# PicoMiteVGAV1_1.net
KiCad netlist of a schematic drawn in EasyEDA Pro
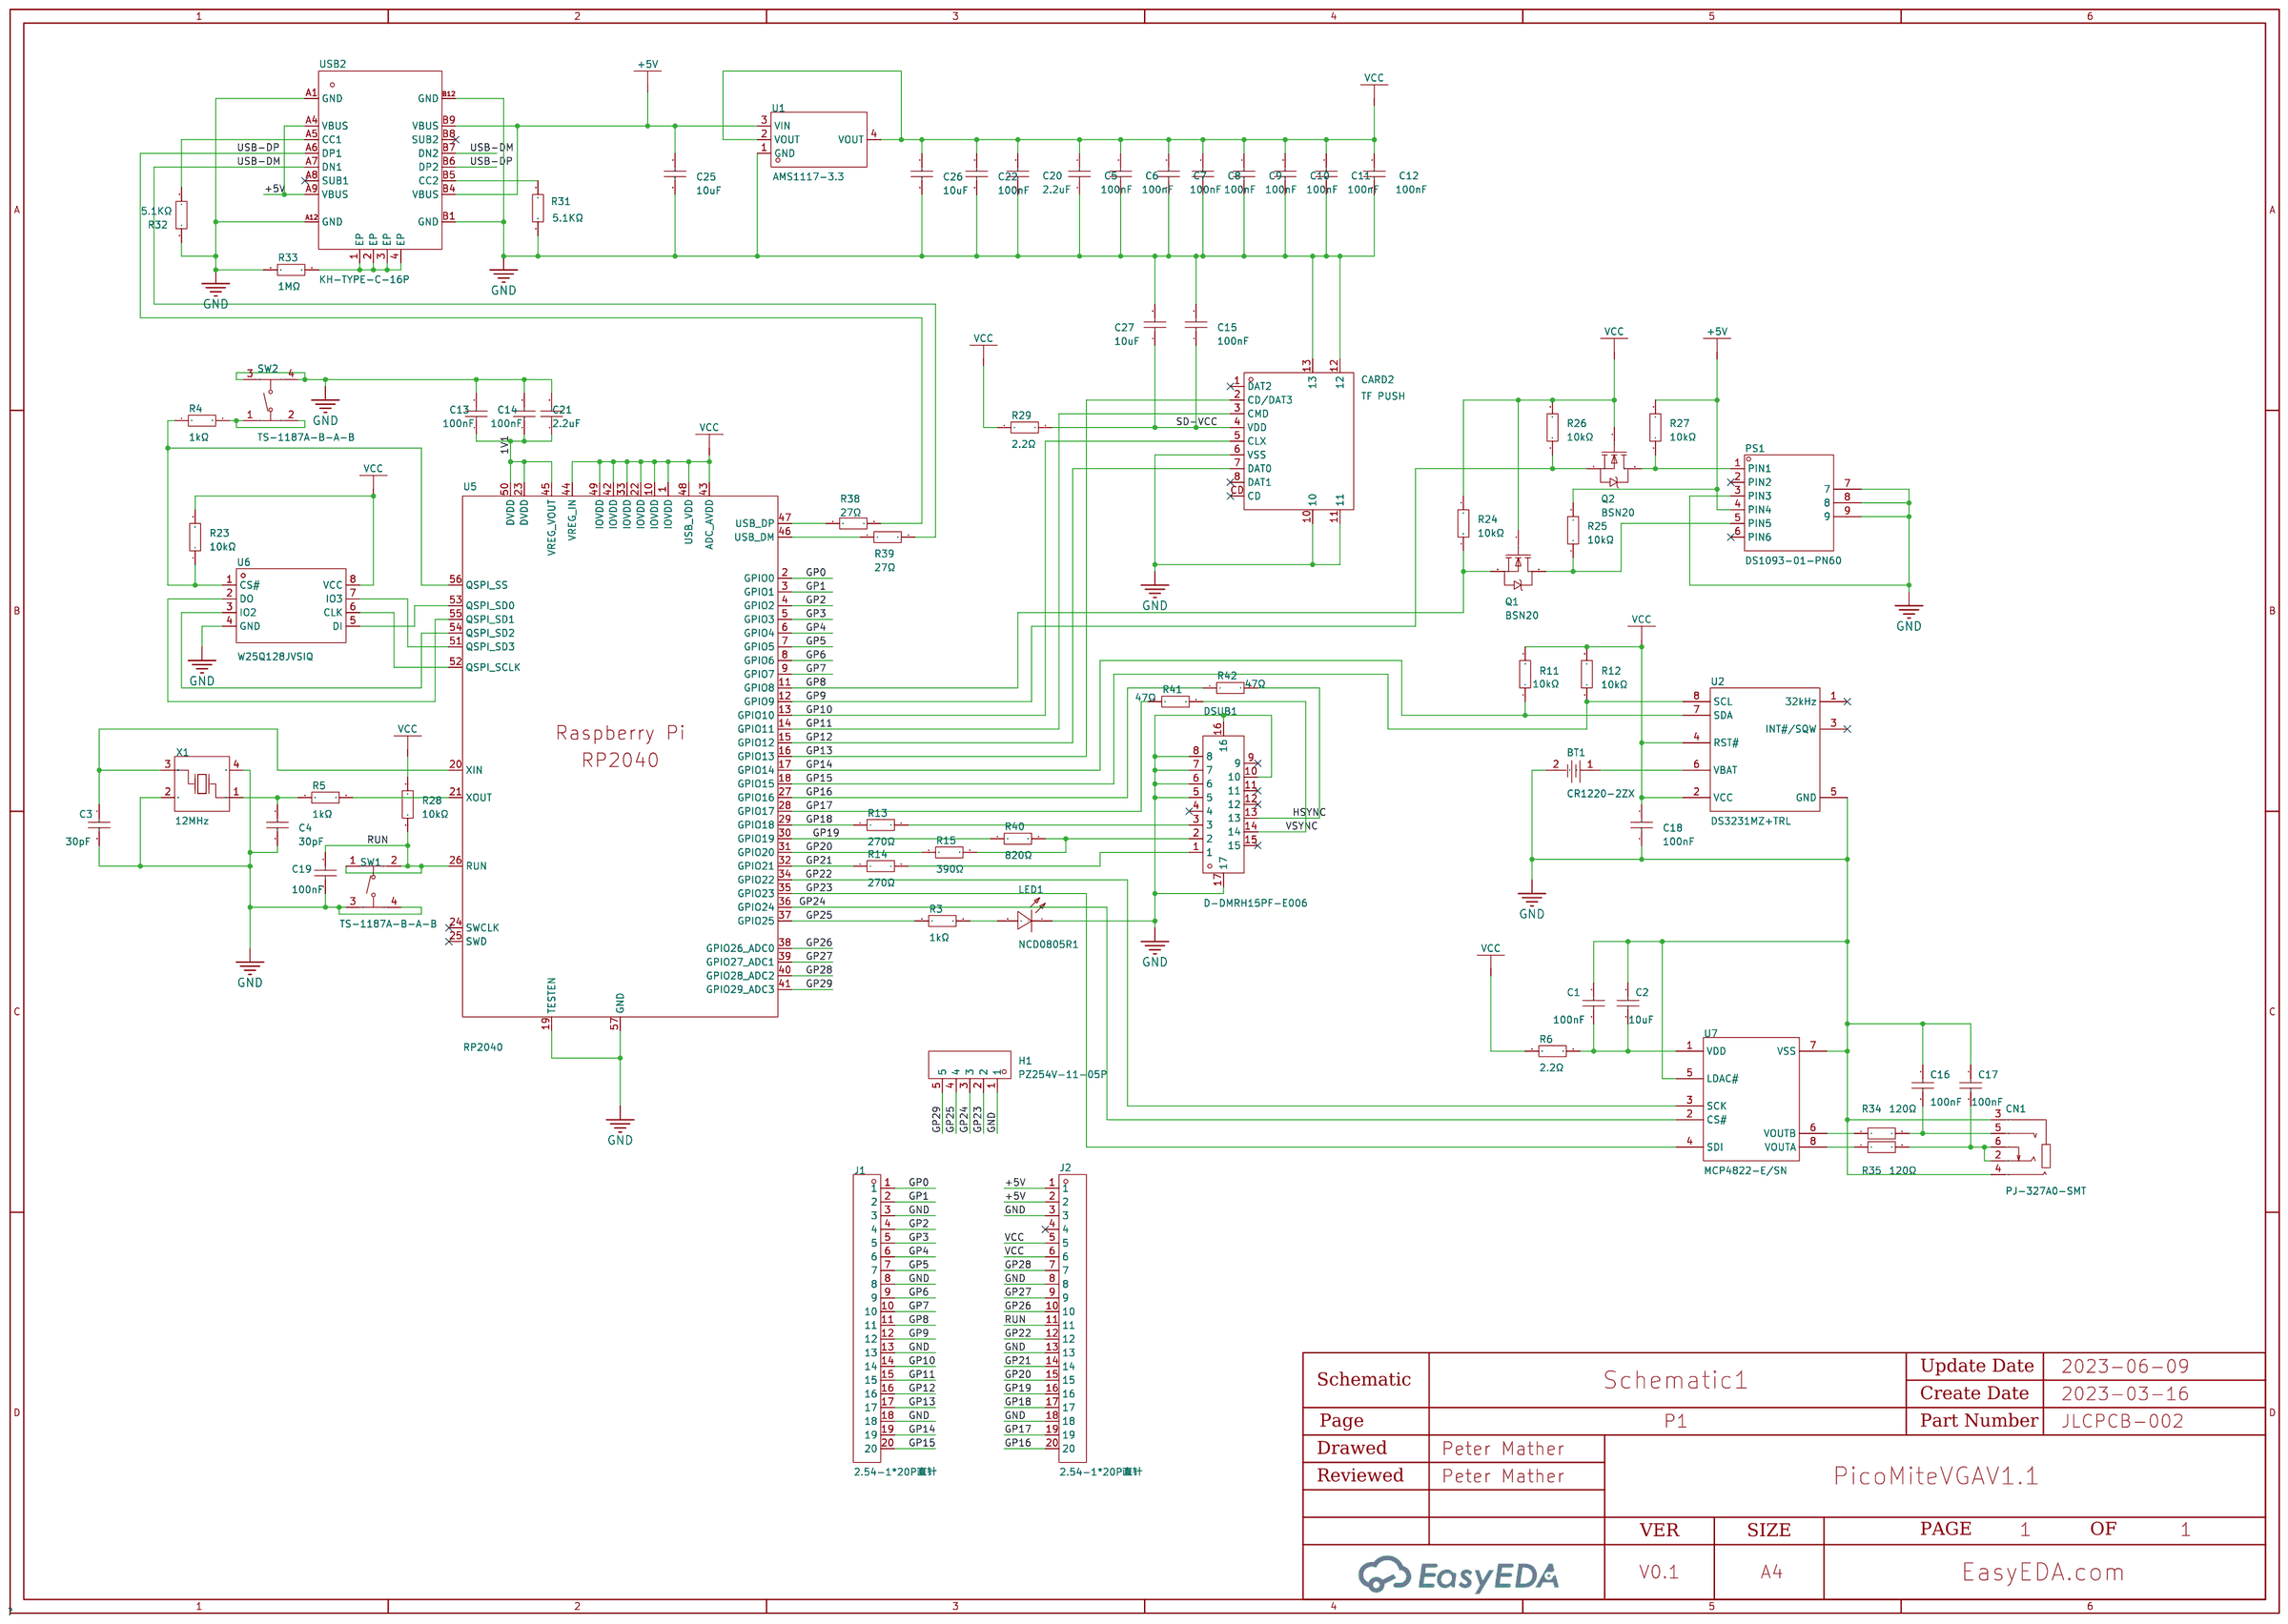
[diagram p0: schematic sheet]

(export (version "E")
  (design (tool "Eeschema 10.0.6"))
  (components
    (comp (ref "BT1")
      (value "CR1220-2ZX")
      (footprint "easyedapro:BAT-SMD_CR1220-2ZX")
      (fields (field (name "Manufacturer") "Q&J"))
      (libsource (lib "easyedapro") (part "CR1220-2ZX"))
    )
    (comp (ref "C1")
      (value "100nF")
      (footprint "easyedapro:C0603")
      (fields
        (field (name "Manufacturer Part") "CL05B104KO5NNNC")
        (field (name "Manufacturer") "SAMSUNG(三星)")
      )
      (libsource (lib "easyedapro") (part "CL10A225KO8NNNC"))
    )
    (comp (ref "C2")
      (value "10uF")
      (footprint "easyedapro:C1206")
      (fields
        (field (name "Manufacturer Part") "CL31A106KBHNNNE")
        (field (name "Manufacturer") "SAMSUNG(三星)")
      )
      (libsource (lib "easyedapro") (part "CL31A106KBHNNNE"))
    )
    (comp (ref "C3")
      (value "30pF")
      (footprint "easyedapro:C0805")
      (fields (field (name "Manufacturer Part") "0402CG300J500NT") (field (name "Manufacturer") "FH(风华)"))
      (libsource (lib "easyedapro") (part "CC0805JRNPO9BN300"))
    )
    (comp (ref "C4")
      (value "30pF")
      (footprint "easyedapro:C0805")
      (fields (field (name "Manufacturer Part") "0402CG300J500NT") (field (name "Manufacturer") "FH(风华)"))
      (libsource (lib "easyedapro") (part "CC0805JRNPO9BN300"))
    )
    (comp (ref "C5")
      (value "100nF")
      (footprint "easyedapro:C0603")
      (fields
        (field (name "Manufacturer Part") "CL05B104KO5NNNC")
        (field (name "Manufacturer") "SAMSUNG(三星)")
      )
      (libsource (lib "easyedapro") (part "CL10A225KO8NNNC"))
    )
    (comp (ref "C6")
      (value "100nF")
      (footprint "easyedapro:C0603")
      (fields
        (field (name "Manufacturer Part") "CL05B104KO5NNNC")
        (field (name "Manufacturer") "SAMSUNG(三星)")
      )
      (libsource (lib "easyedapro") (part "CL10A225KO8NNNC"))
    )
    (comp (ref "C7")
      (value "100nF")
      (footprint "easyedapro:C0603")
      (fields
        (field (name "Manufacturer Part") "CL05B104KO5NNNC")
        (field (name "Manufacturer") "SAMSUNG(三星)")
      )
      (libsource (lib "easyedapro") (part "CL10A225KO8NNNC"))
    )
    (comp (ref "C8")
      (value "100nF")
      (footprint "easyedapro:C0603")
      (fields
        (field (name "Manufacturer Part") "CL05B104KO5NNNC")
        (field (name "Manufacturer") "SAMSUNG(三星)")
      )
      (libsource (lib "easyedapro") (part "CL10A225KO8NNNC"))
    )
    (comp (ref "C9")
      (value "100nF")
      (footprint "easyedapro:C0603")
      (fields
        (field (name "Manufacturer Part") "CL05B104KO5NNNC")
        (field (name "Manufacturer") "SAMSUNG(三星)")
      )
      (libsource (lib "easyedapro") (part "CL10A225KO8NNNC"))
    )
    (comp (ref "C10")
      (value "100nF")
      (footprint "easyedapro:C0603")
      (fields
        (field (name "Manufacturer Part") "CL05B104KO5NNNC")
        (field (name "Manufacturer") "SAMSUNG(三星)")
      )
      (libsource (lib "easyedapro") (part "CL10A225KO8NNNC"))
    )
    (comp (ref "C11")
      (value "100nF")
      (footprint "easyedapro:C0603")
      (fields
        (field (name "Manufacturer Part") "CL05B104KO5NNNC")
        (field (name "Manufacturer") "SAMSUNG(三星)")
      )
      (libsource (lib "easyedapro") (part "CL10A225KO8NNNC"))
    )
    (comp (ref "C12")
      (value "100nF")
      (footprint "easyedapro:C0603")
      (fields
        (field (name "Manufacturer Part") "CL05B104KO5NNNC")
        (field (name "Manufacturer") "SAMSUNG(三星)")
      )
      (libsource (lib "easyedapro") (part "CL10A225KO8NNNC"))
    )
    (comp (ref "C13")
      (value "100nF")
      (footprint "easyedapro:C0603")
      (fields
        (field (name "Manufacturer Part") "CL05B104KO5NNNC")
        (field (name "Manufacturer") "SAMSUNG(三星)")
      )
      (libsource (lib "easyedapro") (part "CL10A225KO8NNNC"))
    )
    (comp (ref "C14")
      (value "100nF")
      (footprint "easyedapro:C0603")
      (fields
        (field (name "Manufacturer Part") "CL05B104KO5NNNC")
        (field (name "Manufacturer") "SAMSUNG(三星)")
      )
      (libsource (lib "easyedapro") (part "CL10A225KO8NNNC"))
    )
    (comp (ref "C15")
      (value "100nF")
      (footprint "easyedapro:C0603")
      (fields
        (field (name "Manufacturer Part") "CL05B104KO5NNNC")
        (field (name "Manufacturer") "SAMSUNG(三星)")
      )
      (libsource (lib "easyedapro") (part "CL10A225KO8NNNC"))
    )
    (comp (ref "C16")
      (value "100nF")
      (footprint "easyedapro:C0603")
      (fields
        (field (name "Manufacturer Part") "CL05B104KO5NNNC")
        (field (name "Manufacturer") "SAMSUNG(三星)")
      )
      (libsource (lib "easyedapro") (part "CL10A225KO8NNNC"))
    )
    (comp (ref "C17")
      (value "100nF")
      (footprint "easyedapro:C0603")
      (fields
        (field (name "Manufacturer Part") "CL05B104KO5NNNC")
        (field (name "Manufacturer") "SAMSUNG(三星)")
      )
      (libsource (lib "easyedapro") (part "CL10A225KO8NNNC"))
    )
    (comp (ref "C18")
      (value "100nF")
      (footprint "easyedapro:C0603")
      (fields
        (field (name "Manufacturer Part") "CL05B104KO5NNNC")
        (field (name "Manufacturer") "SAMSUNG(三星)")
      )
      (libsource (lib "easyedapro") (part "CL10A225KO8NNNC"))
    )
    (comp (ref "C19")
      (value "100nF")
      (footprint "easyedapro:C0603")
      (fields
        (field (name "Manufacturer Part") "CL05B104KO5NNNC")
        (field (name "Manufacturer") "SAMSUNG(三星)")
      )
      (libsource (lib "easyedapro") (part "CL10A225KO8NNNC"))
    )
    (comp (ref "C20")
      (value "2.2uF")
      (footprint "easyedapro:C0402_NEW")
      (fields
        (field (name "Manufacturer Part") "CL10A225KO8NNNC")
        (field (name "Manufacturer") "SAMSUNG(三星)")
      )
      (libsource (lib "easyedapro") (part "CL05B104KO5NNNC"))
    )
    (comp (ref "C21")
      (value "2.2uF")
      (footprint "easyedapro:C0402_NEW")
      (fields
        (field (name "Manufacturer Part") "CL10A225KO8NNNC")
        (field (name "Manufacturer") "SAMSUNG(三星)")
      )
      (libsource (lib "easyedapro") (part "CL05B104KO5NNNC"))
    )
    (comp (ref "C22")
      (value "100nF")
      (footprint "easyedapro:C0603")
      (fields
        (field (name "Manufacturer Part") "CL05B104KO5NNNC")
        (field (name "Manufacturer") "SAMSUNG(三星)")
      )
      (libsource (lib "easyedapro") (part "CL10A225KO8NNNC"))
    )
    (comp (ref "C25")
      (value "10uF")
      (footprint "easyedapro:C1206")
      (fields
        (field (name "Manufacturer Part") "CL31A106KBHNNNE")
        (field (name "Manufacturer") "SAMSUNG(三星)")
      )
      (libsource (lib "easyedapro") (part "CL31A106KBHNNNE"))
    )
    (comp (ref "C26")
      (value "10uF")
      (footprint "easyedapro:C1206")
      (fields
        (field (name "Manufacturer Part") "CL31A106KBHNNNE")
        (field (name "Manufacturer") "SAMSUNG(三星)")
      )
      (libsource (lib "easyedapro") (part "CL31A106KBHNNNE"))
    )
    (comp (ref "C27")
      (value "10uF")
      (footprint "easyedapro:C1206")
      (fields
        (field (name "Manufacturer Part") "CL31A106KBHNNNE")
        (field (name "Manufacturer") "SAMSUNG(三星)")
      )
      (libsource (lib "easyedapro") (part "CL31A106KBHNNNE"))
    )
    (comp (ref "CARD2")
      (value "TF PUSH")
      (footprint "easyedapro:TF-SMD_TF-PUSH")
      (fields (field (name "Manufacturer") "SHOU HAN(首韩)"))
      (libsource (lib "easyedapro") (part "TF PUSH"))
    )
    (comp (ref "CN1")
      (value "PJ-327A0-SMT")
      (footprint "easyedapro:AUDIO-SMD_PJ-327A0-SMT")
      (fields (field (name "Manufacturer") "XKB Connectivity(中国星坤)"))
      (libsource (lib "easyedapro") (part "PJ-327A0-SMT"))
    )
    (comp (ref "DSUB1")
      (value "D-DMRH15PF-E006")
      (footprint "easyedapro:DSUB-TH_15P-P2.29-H-F_DDMRH15PFE006")
      (fields (field (name "Manufacturer") "Ckmtw(灿科盟)"))
      (libsource (lib "easyedapro") (part "DDMRH15PFE006"))
    )
    (comp (ref "H1")
      (value "PZ254V-11-05P")
      (footprint "easyedapro:HDR-TH_5P-P2.54-V-M")
      (fields (field (name "Manufacturer") "XFCN(兴飞)"))
      (libsource (lib "easyedapro") (part "PZ254V-11-05P"))
    )
    (comp (ref "J1")
      (value "2.54-1*20P直针")
      (footprint "easyedapro:HDR-TH_20P-P2.54-V-M-1")
      (fields (field (name "Manufacturer") "BOOMELE(博穆精密)"))
      (libsource (lib "easyedapro") (part "Header-Male-2.54_1x20"))
    )
    (comp (ref "J2")
      (value "2.54-1*20P直针")
      (footprint "easyedapro:HDR-TH_20P-P2.54-V-M-1")
      (fields (field (name "Manufacturer") "BOOMELE(博穆精密)"))
      (libsource (lib "easyedapro") (part "Header-Male-2.54_1x20"))
    )
    (comp (ref "LED1")
      (value "NCD0805R1")
      (footprint "easyedapro:LED0805-RD")
      (description "Emitted Color:红灯")
      (fields (field (name "Manufacturer") "国星光电"))
      (libsource (lib "easyedapro") (part "FC-2012HRK-620D"))
    )
    (comp (ref "PS1")
      (value "DS1093-01-PN60")
      (footprint "easyedapro:CONN-TH_DS1093-01-PN60")
      (fields (field (name "Manufacturer") "CONNFLY"))
      (libsource (lib "easyedapro") (part "DS1093-01-PN60"))
    )
    (comp (ref "Q1")
      (value "BSN20")
      (footprint "easyedapro:SOT-23-3_L2.9-W1.6-P1.90-LS2.8-BR")
      (fields (field (name "Manufacturer") "SHIKUES(时科)"))
      (libsource (lib "easyedapro") (part "BSN20"))
    )
    (comp (ref "Q2")
      (value "BSN20")
      (footprint "easyedapro:SOT-23-3_L2.9-W1.6-P1.90-LS2.8-BR")
      (fields (field (name "Manufacturer") "SHIKUES(时科)"))
      (libsource (lib "easyedapro") (part "BSN20"))
    )
    (comp (ref "R3")
      (value "1kΩ")
      (footprint "easyedapro:R0603")
      (fields
        (field (name "Manufacturer Part") "0603WAF1001T5E")
        (field (name "Manufacturer") "UNI-ROYAL(厚声)")
      )
      (libsource (lib "easyedapro") (part "0603WAF1001T5E"))
    )
    (comp (ref "R4")
      (value "1kΩ")
      (footprint "easyedapro:R0603")
      (fields
        (field (name "Manufacturer Part") "0603WAF1001T5E")
        (field (name "Manufacturer") "UNI-ROYAL(厚声)")
      )
      (libsource (lib "easyedapro") (part "0603WAF1001T5E"))
    )
    (comp (ref "R5")
      (value "1kΩ")
      (footprint "easyedapro:R0603")
      (fields
        (field (name "Manufacturer Part") "0603WAF1001T5E")
        (field (name "Manufacturer") "UNI-ROYAL(厚声)")
      )
      (libsource (lib "easyedapro") (part "0603WAF1001T5E"))
    )
    (comp (ref "R6")
      (value "2.2Ω")
      (footprint "easyedapro:R0805")
      (fields (field (name "Manufacturer") "UNI-ROYAL(厚声)"))
      (libsource (lib "easyedapro") (part "0805W8F220KT5E"))
    )
    (comp (ref "R11")
      (value "10kΩ")
      (footprint "easyedapro:R0805")
      (fields
        (field (name "Manufacturer Part") "0805W8F1002T5E")
        (field (name "Manufacturer") "UNI-ROYAL(厚声)")
      )
      (libsource (lib "easyedapro") (part "0805W8F1002T5E"))
    )
    (comp (ref "R12")
      (value "10kΩ")
      (footprint "easyedapro:R0805")
      (fields
        (field (name "Manufacturer Part") "0805W8F1002T5E")
        (field (name "Manufacturer") "UNI-ROYAL(厚声)")
      )
      (libsource (lib "easyedapro") (part "0805W8F1002T5E"))
    )
    (comp (ref "R13")
      (value "270Ω")
      (footprint "easyedapro:R0603")
      (fields
        (field (name "Manufacturer Part") "0603WAF2700T5E")
        (field (name "Manufacturer") "UNI-ROYAL(厚声)")
      )
      (libsource (lib "easyedapro") (part "0603WAF2700T5E"))
    )
    (comp (ref "R14")
      (value "270Ω")
      (footprint "easyedapro:R0603")
      (fields
        (field (name "Manufacturer Part") "0603WAF2700T5E")
        (field (name "Manufacturer") "UNI-ROYAL(厚声)")
      )
      (libsource (lib "easyedapro") (part "0603WAF2700T5E"))
    )
    (comp (ref "R15")
      (value "390Ω")
      (footprint "easyedapro:R0603")
      (fields
        (field (name "Manufacturer Part") "0603WAF3900T5E")
        (field (name "Manufacturer") "UNI-ROYAL(厚声)")
      )
      (libsource (lib "easyedapro") (part "0603WAF3900T5E"))
    )
    (comp (ref "R23")
      (value "10kΩ")
      (footprint "easyedapro:R0402")
      (fields
        (field (name "Manufacturer Part") "0402WGF1002TCE")
        (field (name "Manufacturer") "UNI-ROYAL(厚声)")
      )
      (libsource (lib "easyedapro") (part "0402WGF1002TCE"))
    )
    (comp (ref "R24")
      (value "10kΩ")
      (footprint "easyedapro:R0402")
      (fields
        (field (name "Manufacturer Part") "0402WGF1002TCE")
        (field (name "Manufacturer") "UNI-ROYAL(厚声)")
      )
      (libsource (lib "easyedapro") (part "0402WGF1002TCE"))
    )
    (comp (ref "R25")
      (value "10kΩ")
      (footprint "easyedapro:R0402")
      (fields
        (field (name "Manufacturer Part") "0402WGF1002TCE")
        (field (name "Manufacturer") "UNI-ROYAL(厚声)")
      )
      (libsource (lib "easyedapro") (part "0402WGF1002TCE"))
    )
    (comp (ref "R26")
      (value "10kΩ")
      (footprint "easyedapro:R0402")
      (fields
        (field (name "Manufacturer Part") "0402WGF1002TCE")
        (field (name "Manufacturer") "UNI-ROYAL(厚声)")
      )
      (libsource (lib "easyedapro") (part "0402WGF1002TCE"))
    )
    (comp (ref "R27")
      (value "10kΩ")
      (footprint "easyedapro:R0402")
      (fields
        (field (name "Manufacturer Part") "0402WGF1002TCE")
        (field (name "Manufacturer") "UNI-ROYAL(厚声)")
      )
      (libsource (lib "easyedapro") (part "0402WGF1002TCE"))
    )
    (comp (ref "R28")
      (value "10kΩ")
      (footprint "easyedapro:R0402")
      (fields
        (field (name "Manufacturer Part") "0402WGF1002TCE")
        (field (name "Manufacturer") "UNI-ROYAL(厚声)")
      )
      (libsource (lib "easyedapro") (part "0402WGF1002TCE"))
    )
    (comp (ref "R29")
      (value "2.2Ω")
      (footprint "easyedapro:R0805")
      (fields (field (name "Manufacturer") "UNI-ROYAL(厚声)"))
      (libsource (lib "easyedapro") (part "0805W8F220KT5E"))
    )
    (comp (ref "R31")
      (value "5.1kΩ")
      (footprint "easyedapro:R0603")
      (fields
        (field (name "Manufacturer Part") "5.1KΩ")
        (field (name "Manufacturer") "UNI-ROYAL(厚声)")
        (field (name "Tolerance") "±1%")
      )
      (libsource (lib "easyedapro") (part "0603WAF5101T5E"))
    )
    (comp (ref "R32")
      (value "5.1kΩ")
      (footprint "easyedapro:R0603")
      (fields
        (field (name "Manufacturer Part") "5.1KΩ")
        (field (name "Manufacturer") "UNI-ROYAL(厚声)")
        (field (name "Tolerance") "±1%")
      )
      (libsource (lib "easyedapro") (part "0603WAF5101T5E"))
    )
    (comp (ref "R33")
      (value "1MΩ")
      (footprint "easyedapro:R0603")
      (fields
        (field (name "Manufacturer Part") "0402WGF1004TCE")
        (field (name "Manufacturer") "UNI-ROYAL(厚声)")
        (field (name "Tolerance") "±1%")
      )
      (libsource (lib "easyedapro") (part "0603WAF1004T5E"))
    )
    (comp (ref "R34")
      (value "120Ω")
      (footprint "easyedapro:R0603")
      (fields
        (field (name "Manufacturer Part") "0603WAF1200T5E")
        (field (name "Manufacturer") "UNI-ROYAL(厚声)")
      )
      (libsource (lib "easyedapro") (part "0603WAF1200T5E"))
    )
    (comp (ref "R35")
      (value "120Ω")
      (footprint "easyedapro:R0603")
      (fields
        (field (name "Manufacturer Part") "0603WAF1200T5E")
        (field (name "Manufacturer") "UNI-ROYAL(厚声)")
      )
      (libsource (lib "easyedapro") (part "0603WAF1200T5E"))
    )
    (comp (ref "R38")
      (value "27Ω")
      (footprint "easyedapro:R0603")
      (fields
        (field (name "Manufacturer Part") "0603WAF270JT5E")
        (field (name "Manufacturer") "UNI-ROYAL(厚声)")
      )
      (libsource (lib "easyedapro") (part "0603WAF270JT5E"))
    )
    (comp (ref "R39")
      (value "27Ω")
      (footprint "easyedapro:R0603")
      (fields
        (field (name "Manufacturer Part") "0603WAF270JT5E")
        (field (name "Manufacturer") "UNI-ROYAL(厚声)")
      )
      (libsource (lib "easyedapro") (part "0603WAF270JT5E"))
    )
    (comp (ref "R40")
      (value "820Ω")
      (footprint "easyedapro:R0603")
      (fields
        (field (name "Manufacturer Part") "0603WAF8200T5E")
        (field (name "Manufacturer") "UNI-ROYAL(厚声)")
      )
      (libsource (lib "easyedapro") (part "0603WAF8200T5E"))
    )
    (comp (ref "R41")
      (value "47Ω")
      (footprint "easyedapro:R0805")
      (fields
        (field (name "Manufacturer Part") "0805W8F470JT5E")
        (field (name "Manufacturer") "UNI-ROYAL(厚声)")
      )
      (libsource (lib "easyedapro") (part "0805W8F470JT5E"))
    )
    (comp (ref "R42")
      (value "47Ω")
      (footprint "easyedapro:R0805")
      (fields
        (field (name "Manufacturer Part") "0805W8F470JT5E")
        (field (name "Manufacturer") "UNI-ROYAL(厚声)")
      )
      (libsource (lib "easyedapro") (part "0805W8F470JT5E"))
    )
    (comp (ref "SW1")
      (value "TS-1187A-B-A-B")
      (footprint "easyedapro:SW-SMD_4P-L5.1-W5.1-P3.70-LS6.5-TL-2")
      (fields (field (name "Manufacturer") "XKB Connectivity(中国星坤)"))
      (libsource (lib "easyedapro") (part "TS-1187A-B-A-B"))
    )
    (comp (ref "SW2")
      (value "TS-1187A-B-A-B")
      (footprint "easyedapro:SW-SMD_4P-L5.1-W5.1-P3.70-LS6.5-TL-2")
      (fields (field (name "Manufacturer") "XKB Connectivity(中国星坤)"))
      (libsource (lib "easyedapro") (part "TS-1187A-B-A-B"))
    )
    (comp (ref "U1")
      (value "AMS1117-3.3")
      (footprint "easyedapro:SOT-223-3_L6.5-W3.4-P2.30-LS7.0-BR")
      (fields (field (name "Manufacturer") "AMS"))
      (libsource (lib "easyedapro") (part "AMS1117-3.3"))
    )
    (comp (ref "U2")
      (value "DS3231MZ+TRL")
      (footprint "easyedapro:SOIC-8_L4.9-W3.9-P1.27-LS6.0-BL")
      (fields (field (name "Manufacturer") "MAXIM(美信)"))
      (libsource (lib "easyedapro") (part "DS3231MZ+"))
    )
    (comp (ref "U5")
      (value "RP2040")
      (footprint "easyedapro:LQFN-56_L7.0-W7.0-P0.4-EP")
      (fields (field (name "Manufacturer") "Raspberry Pi(树莓派)"))
      (libsource (lib "easyedapro") (part "RP2040"))
    )
    (comp (ref "U6")
      (value "W25Q128JVSIQ")
      (footprint "easyedapro:SOIC-8_L5.3-W5.3-P1.27-LS8.0-BL")
      (fields (field (name "Manufacturer") "WINBOND(华邦)"))
      (libsource (lib "easyedapro") (part "W25Q128JVSIQTR"))
    )
    (comp (ref "U7")
      (value "MCP4822-E/SN")
      (footprint "easyedapro:SOIC-8_L4.9-W3.9-P1.27-LS6.0-BL")
      (fields (field (name "Manufacturer") "MICROCHIP(美国微芯)"))
      (libsource (lib "easyedapro") (part "MCP4822-E/SN"))
    )
    (comp (ref "USB2")
      (value "KH-TYPE-C-16P")
      (footprint "easyedapro:USB-C-SMD_KH-TYPE-C-16P")
      (fields (field (name "Manufacturer") "kinghelm(金航标)"))
      (libsource (lib "easyedapro") (part "KH-TYPE-C-16P"))
    )
    (comp (ref "X1")
      (value "12MHz")
      (footprint "easyedapro:OSC-SMD_4P-L3.2-W2.5-BL")
      (fields (field (name "Manufacturer Part") "X322512MSB4SI") (field (name "Manufacturer") "YXC(扬兴晶振)"))
      (libsource (lib "easyedapro") (part "X322512MSB4SI"))
    )
  )
  (nets
    (net (code "1") (name "+5V") (class "Default")
      (node (ref "C25") (pin "2") (pinfunction "2_2") (pintype "input"))
      (node (ref "J2") (pin "1") (pinfunction "1_1") (pintype "input"))
      (node (ref "J2") (pin "2") (pinfunction "2_2") (pintype "input"))
      (node (ref "PS1") (pin "4") (pinfunction "PIN4_4") (pintype "input"))
      (node (ref "R25") (pin "2") (pinfunction "2_2") (pintype "input"))
      (node (ref "R27") (pin "2") (pinfunction "2_2") (pintype "input"))
      (node (ref "U1") (pin "3") (pinfunction "VIN_3") (pintype "input"))
      (node (ref "USB2") (pin "A4") (pinfunction "VBUS_A4") (pintype "input"))
      (node (ref "USB2") (pin "A9") (pinfunction "VBUS_A9") (pintype "input"))
      (node (ref "USB2") (pin "B4") (pinfunction "VBUS_B4") (pintype "input"))
      (node (ref "USB2") (pin "B9") (pinfunction "VBUS_B9") (pintype "input"))
    )
    (net (code "2") (name "/1V1") (class "Default")
      (node (ref "C13") (pin "1") (pinfunction "1_1") (pintype "input"))
      (node (ref "C14") (pin "1") (pinfunction "1_1") (pintype "input"))
      (node (ref "C21") (pin "1") (pinfunction "1_1") (pintype "input"))
      (node (ref "U5") (pin "23") (pinfunction "DVDD_23") (pintype "bidirectional"))
      (node (ref "U5") (pin "45") (pinfunction "VREG_VOUT_45") (pintype "bidirectional"))
      (node (ref "U5") (pin "50") (pinfunction "DVDD_50") (pintype "bidirectional"))
    )
    (net (code "3") (name "/GP0") (class "Default")
      (node (ref "J1") (pin "1") (pinfunction "1_1") (pintype "input"))
      (node (ref "U5") (pin "2") (pinfunction "GPIO0_2") (pintype "bidirectional"))
    )
    (net (code "4") (name "/GP1") (class "Default")
      (node (ref "J1") (pin "2") (pinfunction "2_2") (pintype "input"))
      (node (ref "U5") (pin "3") (pinfunction "GPIO1_3") (pintype "bidirectional"))
    )
    (net (code "5") (name "/GP2") (class "Default")
      (node (ref "J1") (pin "4") (pinfunction "4_4") (pintype "input"))
      (node (ref "U5") (pin "4") (pinfunction "GPIO2_4") (pintype "bidirectional"))
    )
    (net (code "6") (name "/GP3") (class "Default")
      (node (ref "J1") (pin "5") (pinfunction "5_5") (pintype "input"))
      (node (ref "U5") (pin "5") (pinfunction "GPIO3_5") (pintype "bidirectional"))
    )
    (net (code "7") (name "/GP4") (class "Default")
      (node (ref "J1") (pin "6") (pinfunction "6_6") (pintype "input"))
      (node (ref "U5") (pin "6") (pinfunction "GPIO4_6") (pintype "bidirectional"))
    )
    (net (code "8") (name "/GP5") (class "Default")
      (node (ref "J1") (pin "7") (pinfunction "7_7") (pintype "input"))
      (node (ref "U5") (pin "7") (pinfunction "GPIO5_7") (pintype "bidirectional"))
    )
    (net (code "9") (name "/GP6") (class "Default")
      (node (ref "J1") (pin "9") (pinfunction "9_9") (pintype "input"))
      (node (ref "U5") (pin "8") (pinfunction "GPIO6_8") (pintype "bidirectional"))
    )
    (net (code "10") (name "/GP7") (class "Default")
      (node (ref "J1") (pin "10") (pinfunction "10_10") (pintype "input"))
      (node (ref "U5") (pin "9") (pinfunction "GPIO7_9") (pintype "bidirectional"))
    )
    (net (code "11") (name "/GP8") (class "Default")
      (node (ref "J1") (pin "11") (pinfunction "11_11") (pintype "input"))
      (node (ref "Q1") (pin "2") (pinfunction "S_2") (pintype "input"))
      (node (ref "R24") (pin "1") (pinfunction "1_1") (pintype "input"))
      (node (ref "U5") (pin "11") (pinfunction "GPIO8_11") (pintype "bidirectional"))
    )
    (net (code "12") (name "/GP9") (class "Default")
      (node (ref "J1") (pin "12") (pinfunction "12_12") (pintype "input"))
      (node (ref "Q2") (pin "2") (pinfunction "S_2") (pintype "input"))
      (node (ref "R26") (pin "1") (pinfunction "1_1") (pintype "input"))
      (node (ref "U5") (pin "12") (pinfunction "GPIO9_12") (pintype "bidirectional"))
    )
    (net (code "13") (name "/GP10") (class "Default")
      (node (ref "CARD2") (pin "5") (pinfunction "CLX_5") (pintype "input"))
      (node (ref "J1") (pin "14") (pinfunction "14_14") (pintype "input"))
      (node (ref "U5") (pin "13") (pinfunction "GPIO10_13") (pintype "bidirectional"))
    )
    (net (code "14") (name "/GP11") (class "Default")
      (node (ref "CARD2") (pin "3") (pinfunction "CMD_3") (pintype "input"))
      (node (ref "J1") (pin "15") (pinfunction "15_15") (pintype "input"))
      (node (ref "U5") (pin "14") (pinfunction "GPIO11_14") (pintype "bidirectional"))
    )
    (net (code "15") (name "/GP12") (class "Default")
      (node (ref "CARD2") (pin "7") (pinfunction "DAT0_7") (pintype "input"))
      (node (ref "J1") (pin "16") (pinfunction "16_16") (pintype "input"))
      (node (ref "U5") (pin "15") (pinfunction "GPIO12_15") (pintype "bidirectional"))
    )
    (net (code "16") (name "/GP13") (class "Default")
      (node (ref "CARD2") (pin "2") (pinfunction "CD/DAT3_2") (pintype "input"))
      (node (ref "J1") (pin "17") (pinfunction "17_17") (pintype "input"))
      (node (ref "U5") (pin "16") (pinfunction "GPIO13_16") (pintype "bidirectional"))
    )
    (net (code "17") (name "/GP14") (class "Default")
      (node (ref "J1") (pin "19") (pinfunction "19_19") (pintype "input"))
      (node (ref "R11") (pin "1") (pinfunction "1_1") (pintype "input"))
      (node (ref "U2") (pin "7") (pinfunction "SDA_7") (pintype "bidirectional"))
      (node (ref "U5") (pin "17") (pinfunction "GPIO14_17") (pintype "bidirectional"))
    )
    (net (code "18") (name "/GP15") (class "Default")
      (node (ref "J1") (pin "20") (pinfunction "20_20") (pintype "input"))
      (node (ref "R12") (pin "1") (pinfunction "1_1") (pintype "input"))
      (node (ref "U2") (pin "8") (pinfunction "SCL_8") (pintype "input"))
      (node (ref "U5") (pin "18") (pinfunction "GPIO15_18") (pintype "bidirectional"))
    )
    (net (code "19") (name "/GP16") (class "Default")
      (node (ref "J2") (pin "20") (pinfunction "20_20") (pintype "input"))
      (node (ref "R42") (pin "1") (pinfunction "1_1") (pintype "input"))
      (node (ref "U5") (pin "27") (pinfunction "GPIO16_27") (pintype "bidirectional"))
    )
    (net (code "20") (name "/GP17") (class "Default")
      (node (ref "J2") (pin "19") (pinfunction "19_19") (pintype "input"))
      (node (ref "R41") (pin "1") (pinfunction "1_1") (pintype "input"))
      (node (ref "U5") (pin "28") (pinfunction "GPIO17_28") (pintype "bidirectional"))
    )
    (net (code "21") (name "/GP18") (class "Default")
      (node (ref "J2") (pin "17") (pinfunction "17_17") (pintype "input"))
      (node (ref "R13") (pin "1") (pinfunction "1_1") (pintype "input"))
      (node (ref "U5") (pin "29") (pinfunction "GPIO18_29") (pintype "bidirectional"))
    )
    (net (code "22") (name "/GP19") (class "Default")
      (node (ref "J2") (pin "16") (pinfunction "16_16") (pintype "input"))
      (node (ref "R40") (pin "1") (pinfunction "1_1") (pintype "input"))
      (node (ref "U5") (pin "30") (pinfunction "GPIO19_30") (pintype "bidirectional"))
    )
    (net (code "23") (name "/GP20") (class "Default")
      (node (ref "J2") (pin "15") (pinfunction "15_15") (pintype "input"))
      (node (ref "R15") (pin "1") (pinfunction "1_1") (pintype "input"))
      (node (ref "U5") (pin "31") (pinfunction "GPIO20_31") (pintype "bidirectional"))
    )
    (net (code "24") (name "/GP21") (class "Default")
      (node (ref "J2") (pin "14") (pinfunction "14_14") (pintype "input"))
      (node (ref "R14") (pin "1") (pinfunction "1_1") (pintype "input"))
      (node (ref "U5") (pin "32") (pinfunction "GPIO21_32") (pintype "bidirectional"))
    )
    (net (code "25") (name "/GP22") (class "Default")
      (node (ref "J2") (pin "12") (pinfunction "12_12") (pintype "input"))
      (node (ref "U5") (pin "34") (pinfunction "GPIO22_34") (pintype "bidirectional"))
      (node (ref "U7") (pin "3") (pinfunction "SCK_3") (pintype "input"))
    )
    (net (code "26") (name "/GP23") (class "Default")
      (node (ref "H1") (pin "2") (pinfunction "2_2") (pintype "input"))
      (node (ref "U5") (pin "35") (pinfunction "GPIO23_35") (pintype "bidirectional"))
      (node (ref "U7") (pin "4") (pinfunction "SDI_4") (pintype "input"))
    )
    (net (code "27") (name "/GP24") (class "Default")
      (node (ref "H1") (pin "3") (pinfunction "3_3") (pintype "input"))
      (node (ref "U5") (pin "36") (pinfunction "GPIO24_36") (pintype "bidirectional"))
      (node (ref "U7") (pin "2") (pinfunction "CS#_2") (pintype "input"))
    )
    (net (code "28") (name "/GP25") (class "Default")
      (node (ref "H1") (pin "4") (pinfunction "4_4") (pintype "input"))
      (node (ref "R3") (pin "1") (pinfunction "1_1") (pintype "input"))
      (node (ref "U5") (pin "37") (pinfunction "GPIO25_37") (pintype "bidirectional"))
    )
    (net (code "29") (name "/GP26") (class "Default")
      (node (ref "J2") (pin "10") (pinfunction "10_10") (pintype "input"))
      (node (ref "U5") (pin "38") (pinfunction "GPIO26_ADC0_38") (pintype "bidirectional"))
    )
    (net (code "30") (name "/GP27") (class "Default")
      (node (ref "J2") (pin "9") (pinfunction "9_9") (pintype "input"))
      (node (ref "U5") (pin "39") (pinfunction "GPIO27_ADC1_39") (pintype "bidirectional"))
    )
    (net (code "31") (name "/GP28") (class "Default")
      (node (ref "J2") (pin "7") (pinfunction "7_7") (pintype "input"))
      (node (ref "U5") (pin "40") (pinfunction "GPIO28_ADC2_40") (pintype "bidirectional"))
    )
    (net (code "32") (name "/GP29") (class "Default")
      (node (ref "H1") (pin "5") (pinfunction "5_5") (pintype "input"))
      (node (ref "U5") (pin "41") (pinfunction "GPIO29_ADC3_41") (pintype "bidirectional"))
    )
    (net (code "33") (name "/HSYNC") (class "Default")
      (node (ref "DSUB1") (pin "13") (pinfunction "13_13") (pintype "input"))
      (node (ref "R42") (pin "2") (pinfunction "2_2") (pintype "input"))
    )
    (net (code "34") (name "/RUN") (class "Default")
      (node (ref "C19") (pin "2") (pinfunction "2_2") (pintype "input"))
      (node (ref "J2") (pin "11") (pinfunction "11_11") (pintype "input"))
      (node (ref "R28") (pin "1") (pinfunction "1_1") (pintype "input"))
      (node (ref "SW1") (pin "1") (pinfunction "A_1") (pintype "input"))
      (node (ref "SW1") (pin "2") (pinfunction "B_2") (pintype "input"))
      (node (ref "U5") (pin "26") (pinfunction "RUN_26") (pintype "input"))
    )
    (net (code "35") (name "/SD-VCC") (class "Default")
      (node (ref "C15") (pin "1") (pinfunction "1_1") (pintype "input"))
      (node (ref "C27") (pin "1") (pinfunction "1_1") (pintype "input"))
      (node (ref "CARD2") (pin "4") (pinfunction "VDD_4") (pintype "input"))
      (node (ref "R29") (pin "2") (pinfunction "2_2") (pintype "input"))
    )
    (net (code "36") (name "/USB-DM") (class "Default")
      (node (ref "R39") (pin "2") (pinfunction "2_2") (pintype "input"))
      (node (ref "USB2") (pin "A7") (pinfunction "DN1_A7") (pintype "input"))
      (node (ref "USB2") (pin "B7") (pinfunction "DN2_B7") (pintype "input"))
    )
    (net (code "37") (name "/USB-DP") (class "Default")
      (node (ref "R38") (pin "2") (pinfunction "2_2") (pintype "input"))
      (node (ref "USB2") (pin "A6") (pinfunction "DP1_A6") (pintype "input"))
      (node (ref "USB2") (pin "B6") (pinfunction "DP2_B6") (pintype "input"))
    )
    (net (code "38") (name "/VSYNC") (class "Default")
      (node (ref "DSUB1") (pin "14") (pinfunction "14_14") (pintype "input"))
      (node (ref "R41") (pin "2") (pinfunction "2_2") (pintype "input"))
    )
    (net (code "39") (name "GND") (class "Default")
      (node (ref "BT1") (pin "2") (pinfunction "2_2") (pintype "input"))
      (node (ref "C1") (pin "2") (pinfunction "2_2") (pintype "input"))
      (node (ref "C10") (pin "1") (pinfunction "1_1") (pintype "input"))
      (node (ref "C11") (pin "1") (pinfunction "1_1") (pintype "input"))
      (node (ref "C12") (pin "1") (pinfunction "1_1") (pintype "input"))
      (node (ref "C13") (pin "2") (pinfunction "2_2") (pintype "input"))
      (node (ref "C14") (pin "2") (pinfunction "2_2") (pintype "input"))
      (node (ref "C15") (pin "2") (pinfunction "2_2") (pintype "input"))
      (node (ref "C16") (pin "2") (pinfunction "2_2") (pintype "input"))
      (node (ref "C17") (pin "2") (pinfunction "2_2") (pintype "input"))
      (node (ref "C18") (pin "1") (pinfunction "1_1") (pintype "input"))
      (node (ref "C19") (pin "1") (pinfunction "1_1") (pintype "input"))
      (node (ref "C2") (pin "2") (pinfunction "2_2") (pintype "input"))
      (node (ref "C20") (pin "1") (pinfunction "1_1") (pintype "input"))
      (node (ref "C21") (pin "2") (pinfunction "2_2") (pintype "input"))
      (node (ref "C22") (pin "1") (pinfunction "1_1") (pintype "input"))
      (node (ref "C25") (pin "1") (pinfunction "1_1") (pintype "input"))
      (node (ref "C26") (pin "1") (pinfunction "1_1") (pintype "input"))
      (node (ref "C27") (pin "2") (pinfunction "2_2") (pintype "input"))
      (node (ref "C3") (pin "1") (pinfunction "1_1") (pintype "input"))
      (node (ref "C4") (pin "1") (pinfunction "1_1") (pintype "input"))
      (node (ref "C5") (pin "1") (pinfunction "1_1") (pintype "input"))
      (node (ref "C6") (pin "1") (pinfunction "1_1") (pintype "input"))
      (node (ref "C7") (pin "1") (pinfunction "1_1") (pintype "input"))
      (node (ref "C8") (pin "1") (pinfunction "1_1") (pintype "input"))
      (node (ref "C9") (pin "1") (pinfunction "1_1") (pintype "input"))
      (node (ref "CARD2") (pin "10") (pinfunction "10_10") (pintype "input"))
      (node (ref "CARD2") (pin "11") (pinfunction "11_11") (pintype "input"))
      (node (ref "CARD2") (pin "12") (pinfunction "12_12") (pintype "input"))
      (node (ref "CARD2") (pin "13") (pinfunction "13_13") (pintype "input"))
      (node (ref "CARD2") (pin "6") (pinfunction "VSS_6") (pintype "input"))
      (node (ref "CN1") (pin "3") (pinfunction "3_3") (pintype "input"))
      (node (ref "CN1") (pin "4") (pinfunction "4_4") (pintype "input"))
      (node (ref "DSUB1") (pin "10") (pinfunction "10_10") (pintype "input"))
      (node (ref "DSUB1") (pin "16") (pinfunction "16_16") (pintype "input"))
      (node (ref "DSUB1") (pin "17") (pinfunction "17_17") (pintype "input"))
      (node (ref "DSUB1") (pin "5") (pinfunction "5_5") (pintype "input"))
      (node (ref "DSUB1") (pin "6") (pinfunction "6_6") (pintype "input"))
      (node (ref "DSUB1") (pin "7") (pinfunction "7_7") (pintype "input"))
      (node (ref "DSUB1") (pin "8") (pinfunction "8_8") (pintype "input"))
      (node (ref "H1") (pin "1") (pinfunction "1_1") (pintype "input"))
      (node (ref "J1") (pin "13") (pinfunction "13_13") (pintype "input"))
      (node (ref "J1") (pin "18") (pinfunction "18_18") (pintype "input"))
      (node (ref "J1") (pin "3") (pinfunction "3_3") (pintype "input"))
      (node (ref "J1") (pin "8") (pinfunction "8_8") (pintype "input"))
      (node (ref "J2") (pin "13") (pinfunction "13_13") (pintype "input"))
      (node (ref "J2") (pin "18") (pinfunction "18_18") (pintype "input"))
      (node (ref "J2") (pin "3") (pinfunction "3_3") (pintype "input"))
      (node (ref "J2") (pin "8") (pinfunction "8_8") (pintype "input"))
      (node (ref "LED1") (pin "1") (pinfunction "-_1") (pintype "input"))
      (node (ref "PS1") (pin "3") (pinfunction "PIN3_3") (pintype "input"))
      (node (ref "PS1") (pin "7") (pinfunction "7_7") (pintype "input"))
      (node (ref "PS1") (pin "8") (pinfunction "8_8") (pintype "input"))
      (node (ref "PS1") (pin "9") (pinfunction "9_9") (pintype "input"))
      (node (ref "R31") (pin "1") (pinfunction "1_1") (pintype "input"))
      (node (ref "R32") (pin "1") (pinfunction "1_1") (pintype "input"))
      (node (ref "R33") (pin "1") (pinfunction "1_1") (pintype "input"))
      (node (ref "SW1") (pin "3") (pinfunction "C_3") (pintype "input"))
      (node (ref "SW1") (pin "4") (pinfunction "D_4") (pintype "input"))
      (node (ref "SW2") (pin "3") (pinfunction "C_3") (pintype "input"))
      (node (ref "SW2") (pin "4") (pinfunction "D_4") (pintype "input"))
      (node (ref "U1") (pin "1") (pinfunction "GND_1") (pintype "input"))
      (node (ref "U2") (pin "5") (pinfunction "GND_5") (pintype "input"))
      (node (ref "U5") (pin "19") (pinfunction "TESTEN_19") (pintype "input"))
      (node (ref "U5") (pin "57") (pinfunction "GND_57") (pintype "bidirectional"))
      (node (ref "U6") (pin "4") (pinfunction "GND_4") (pintype "input"))
      (node (ref "U7") (pin "5") (pinfunction "LDAC#_5") (pintype "input"))
      (node (ref "U7") (pin "7") (pinfunction "VSS_7") (pintype "input"))
      (node (ref "USB2") (pin "A1") (pinfunction "GND_A1") (pintype "input"))
      (node (ref "USB2") (pin "A12") (pinfunction "GND_A12") (pintype "input"))
      (node (ref "USB2") (pin "B1") (pinfunction "GND_B1") (pintype "input"))
      (node (ref "USB2") (pin "B12") (pinfunction "GND_B12") (pintype "input"))
      (node (ref "X1") (pin "2") (pinfunction "GND_2") (pintype "input"))
      (node (ref "X1") (pin "4") (pinfunction "GND_4") (pintype "input"))
    )
    (net (code "40") (name "Net-(C16-Pad1)") (class "Default")
      (node (ref "C16") (pin "1") (pinfunction "1_1") (pintype "input"))
      (node (ref "CN1") (pin "5") (pinfunction "5_5") (pintype "input"))
      (node (ref "R34") (pin "2") (pinfunction "2_2") (pintype "input"))
    )
    (net (code "41") (name "Net-(C17-Pad1)") (class "Default")
      (node (ref "C17") (pin "1") (pinfunction "1_1") (pintype "input"))
      (node (ref "CN1") (pin "2") (pinfunction "2_2") (pintype "input"))
      (node (ref "CN1") (pin "6") (pinfunction "6_6") (pintype "input"))
      (node (ref "R35") (pin "2") (pinfunction "2_2") (pintype "input"))
    )
    (net (code "42") (name "Net-(DSUB1-Pad1)") (class "Default")
      (node (ref "DSUB1") (pin "1") (pinfunction "1_1") (pintype "input"))
      (node (ref "R14") (pin "2") (pinfunction "2_2") (pintype "input"))
    )
    (net (code "43") (name "Net-(DSUB1-Pad2)") (class "Default")
      (node (ref "DSUB1") (pin "2") (pinfunction "2_2") (pintype "input"))
      (node (ref "R15") (pin "2") (pinfunction "2_2") (pintype "input"))
      (node (ref "R40") (pin "2") (pinfunction "2_2") (pintype "input"))
    )
    (net (code "44") (name "Net-(DSUB1-Pad3)") (class "Default")
      (node (ref "DSUB1") (pin "3") (pinfunction "3_3") (pintype "input"))
      (node (ref "R13") (pin "2") (pinfunction "2_2") (pintype "input"))
    )
    (net (code "45") (name "Net-(LED1-+)") (class "Default")
      (node (ref "LED1") (pin "2") (pinfunction "+_2") (pintype "input"))
      (node (ref "R3") (pin "2") (pinfunction "2_2") (pintype "input"))
    )
    (net (code "46") (name "Net-(PS1-PIN1)") (class "Default")
      (node (ref "PS1") (pin "1") (pinfunction "PIN1_1") (pintype "input"))
      (node (ref "Q2") (pin "3") (pinfunction "D_3") (pintype "input"))
      (node (ref "R27") (pin "1") (pinfunction "1_1") (pintype "input"))
    )
    (net (code "47") (name "Net-(PS1-PIN5)") (class "Default")
      (node (ref "PS1") (pin "5") (pinfunction "PIN5_5") (pintype "input"))
      (node (ref "Q1") (pin "3") (pinfunction "D_3") (pintype "input"))
      (node (ref "R25") (pin "1") (pinfunction "1_1") (pintype "input"))
    )
    (net (code "48") (name "Net-(R33-Pad2)") (class "Default")
      (node (ref "R33") (pin "2") (pinfunction "2_2") (pintype "input"))
      (node (ref "USB2") (pin "1") (pinfunction "EP_1") (pintype "input"))
      (node (ref "USB2") (pin "2") (pinfunction "EP_2") (pintype "input"))
      (node (ref "USB2") (pin "3") (pinfunction "EP_3") (pintype "input"))
      (node (ref "USB2") (pin "4") (pinfunction "EP_4") (pintype "input"))
    )
    (net (code "49") (name "Net-(SW2-A)") (class "Default")
      (node (ref "R4") (pin "2") (pinfunction "2_2") (pintype "input"))
      (node (ref "SW2") (pin "1") (pinfunction "A_1") (pintype "input"))
      (node (ref "SW2") (pin "2") (pinfunction "B_2") (pintype "input"))
    )
    (net (code "50") (name "Net-(U2-VBAT)") (class "Default")
      (node (ref "BT1") (pin "1") (pinfunction "1_1") (pintype "input"))
      (node (ref "U2") (pin "6") (pinfunction "VBAT_6") (pintype "input"))
    )
    (net (code "51") (name "Net-(U5-QSPI_SCLK)") (class "Default")
      (node (ref "U5") (pin "52") (pinfunction "QSPI_SCLK_52") (pintype "output"))
      (node (ref "U6") (pin "6") (pinfunction "CLK_6") (pintype "input"))
    )
    (net (code "52") (name "Net-(U5-QSPI_SD0)") (class "Default")
      (node (ref "U5") (pin "53") (pinfunction "QSPI_SD0_53") (pintype "bidirectional"))
      (node (ref "U6") (pin "5") (pinfunction "DI_5") (pintype "input"))
    )
    (net (code "53") (name "Net-(U5-QSPI_SD1)") (class "Default")
      (node (ref "U5") (pin "55") (pinfunction "QSPI_SD1_55") (pintype "bidirectional"))
      (node (ref "U6") (pin "2") (pinfunction "DO_2") (pintype "input"))
    )
    (net (code "54") (name "Net-(U5-QSPI_SD2)") (class "Default")
      (node (ref "U5") (pin "54") (pinfunction "QSPI_SD2_54") (pintype "bidirectional"))
      (node (ref "U6") (pin "3") (pinfunction "IO2_3") (pintype "input"))
    )
    (net (code "55") (name "Net-(U5-QSPI_SD3)") (class "Default")
      (node (ref "U5") (pin "51") (pinfunction "QSPI_SD3_51") (pintype "bidirectional"))
      (node (ref "U6") (pin "7") (pinfunction "IO3_7") (pintype "input"))
    )
    (net (code "56") (name "Net-(U5-QSPI_SS)") (class "Default")
      (node (ref "R23") (pin "1") (pinfunction "1_1") (pintype "input"))
      (node (ref "R4") (pin "1") (pinfunction "1_1") (pintype "input"))
      (node (ref "U5") (pin "56") (pinfunction "QSPI_SS_56") (pintype "bidirectional"))
      (node (ref "U6") (pin "1") (pinfunction "CS#_1") (pintype "input"))
    )
    (net (code "57") (name "Net-(U5-USB_DM)") (class "Default")
      (node (ref "R39") (pin "1") (pinfunction "1_1") (pintype "input"))
      (node (ref "U5") (pin "46") (pinfunction "USB_DM_46") (pintype "bidirectional"))
    )
    (net (code "58") (name "Net-(U5-USB_DP)") (class "Default")
      (node (ref "R38") (pin "1") (pinfunction "1_1") (pintype "input"))
      (node (ref "U5") (pin "47") (pinfunction "USB_DP_47") (pintype "bidirectional"))
    )
    (net (code "59") (name "Net-(U5-XIN)") (class "Default")
      (node (ref "C3") (pin "2") (pinfunction "2_2") (pintype "input"))
      (node (ref "U5") (pin "20") (pinfunction "XIN_20") (pintype "input"))
      (node (ref "X1") (pin "3") (pinfunction "OSC2_3") (pintype "input"))
    )
    (net (code "60") (name "Net-(U5-XOUT)") (class "Default")
      (node (ref "R5") (pin "2") (pinfunction "2_2") (pintype "input"))
      (node (ref "U5") (pin "21") (pinfunction "XOUT_21") (pintype "input"))
    )
    (net (code "61") (name "Net-(U7-VDD)") (class "Default")
      (node (ref "C1") (pin "1") (pinfunction "1_1") (pintype "input"))
      (node (ref "C2") (pin "1") (pinfunction "1_1") (pintype "input"))
      (node (ref "R6") (pin "2") (pinfunction "2_2") (pintype "input"))
      (node (ref "U7") (pin "1") (pinfunction "VDD_1") (pintype "input"))
    )
    (net (code "62") (name "Net-(U7-VOUTA)") (class "Default")
      (node (ref "R35") (pin "1") (pinfunction "1_1") (pintype "input"))
      (node (ref "U7") (pin "8") (pinfunction "VOUTA_8") (pintype "output"))
    )
    (net (code "63") (name "Net-(U7-VOUTB)") (class "Default")
      (node (ref "R34") (pin "1") (pinfunction "1_1") (pintype "input"))
      (node (ref "U7") (pin "6") (pinfunction "VOUTB_6") (pintype "output"))
    )
    (net (code "64") (name "Net-(USB2-CC1)") (class "Default")
      (node (ref "R32") (pin "2") (pinfunction "2_2") (pintype "input"))
      (node (ref "USB2") (pin "A5") (pinfunction "CC1_A5") (pintype "input"))
    )
    (net (code "65") (name "Net-(USB2-CC2)") (class "Default")
      (node (ref "R31") (pin "2") (pinfunction "2_2") (pintype "input"))
      (node (ref "USB2") (pin "B5") (pinfunction "CC2_B5") (pintype "input"))
    )
    (net (code "66") (name "Net-(X1-OSC1)") (class "Default")
      (node (ref "C4") (pin "2") (pinfunction "2_2") (pintype "input"))
      (node (ref "R5") (pin "1") (pinfunction "1_1") (pintype "input"))
      (node (ref "X1") (pin "1") (pinfunction "OSC1_1") (pintype "input"))
    )
    (net (code "67") (name "VCC") (class "Default")
      (node (ref "C10") (pin "2") (pinfunction "2_2") (pintype "input"))
      (node (ref "C11") (pin "2") (pinfunction "2_2") (pintype "input"))
      (node (ref "C12") (pin "2") (pinfunction "2_2") (pintype "input"))
      (node (ref "C18") (pin "2") (pinfunction "2_2") (pintype "input"))
      (node (ref "C20") (pin "2") (pinfunction "2_2") (pintype "input"))
      (node (ref "C22") (pin "2") (pinfunction "2_2") (pintype "input"))
      (node (ref "C26") (pin "2") (pinfunction "2_2") (pintype "input"))
      (node (ref "C5") (pin "2") (pinfunction "2_2") (pintype "input"))
      (node (ref "C6") (pin "2") (pinfunction "2_2") (pintype "input"))
      (node (ref "C7") (pin "2") (pinfunction "2_2") (pintype "input"))
      (node (ref "C8") (pin "2") (pinfunction "2_2") (pintype "input"))
      (node (ref "C9") (pin "2") (pinfunction "2_2") (pintype "input"))
      (node (ref "J2") (pin "5") (pinfunction "5_5") (pintype "input"))
      (node (ref "J2") (pin "6") (pinfunction "6_6") (pintype "input"))
      (node (ref "Q1") (pin "1") (pinfunction "G_1") (pintype "input"))
      (node (ref "Q2") (pin "1") (pinfunction "G_1") (pintype "input"))
      (node (ref "R11") (pin "2") (pinfunction "2_2") (pintype "input"))
      (node (ref "R12") (pin "2") (pinfunction "2_2") (pintype "input"))
      (node (ref "R23") (pin "2") (pinfunction "2_2") (pintype "input"))
      (node (ref "R24") (pin "2") (pinfunction "2_2") (pintype "input"))
      (node (ref "R26") (pin "2") (pinfunction "2_2") (pintype "input"))
      (node (ref "R28") (pin "2") (pinfunction "2_2") (pintype "input"))
      (node (ref "R29") (pin "1") (pinfunction "1_1") (pintype "input"))
      (node (ref "R6") (pin "1") (pinfunction "1_1") (pintype "input"))
      (node (ref "U1") (pin "2") (pinfunction "VOUT_2") (pintype "input"))
      (node (ref "U1") (pin "4") (pinfunction "VOUT_4") (pintype "input"))
      (node (ref "U2") (pin "2") (pinfunction "VCC_2") (pintype "input"))
      (node (ref "U2") (pin "4") (pinfunction "RST#_4") (pintype "bidirectional"))
      (node (ref "U5") (pin "1") (pinfunction "IOVDD_1") (pintype "bidirectional"))
      (node (ref "U5") (pin "10") (pinfunction "IOVDD_10") (pintype "bidirectional"))
      (node (ref "U5") (pin "22") (pinfunction "IOVDD_22") (pintype "bidirectional"))
      (node (ref "U5") (pin "33") (pinfunction "IOVDD_33") (pintype "bidirectional"))
      (node (ref "U5") (pin "42") (pinfunction "IOVDD_42") (pintype "bidirectional"))
      (node (ref "U5") (pin "43") (pinfunction "ADC_AVDD_43") (pintype "bidirectional"))
      (node (ref "U5") (pin "44") (pinfunction "VREG_IN_44") (pintype "bidirectional"))
      (node (ref "U5") (pin "48") (pinfunction "USB_VDD_48") (pintype "bidirectional"))
      (node (ref "U5") (pin "49") (pinfunction "IOVDD_49") (pintype "bidirectional"))
      (node (ref "U6") (pin "8") (pinfunction "VCC_8") (pintype "input"))
    )
    (net (code "68") (name "unconnected-(CARD2-DAT1-Pad8)") (class "Default")
      (node (ref "CARD2") (pin "8") (pinfunction "DAT1_8") (pintype "input+no_connect"))
    )
    (net (code "69") (name "unconnected-(CARD2-DAT2-Pad1)") (class "Default")
      (node (ref "CARD2") (pin "1") (pinfunction "DAT2_1") (pintype "input+no_connect"))
    )
    (net (code "70") (name "unconnected-(CARD2-PadCD)") (class "Default")
      (node (ref "CARD2") (pin "CD") (pinfunction "CD_CD") (pintype "input+no_connect"))
    )
    (net (code "71") (name "unconnected-(DSUB1-Pad4)") (class "Default")
      (node (ref "DSUB1") (pin "4") (pinfunction "4_4") (pintype "input+no_connect"))
    )
    (net (code "72") (name "unconnected-(DSUB1-Pad9)") (class "Default")
      (node (ref "DSUB1") (pin "9") (pinfunction "9_9") (pintype "input+no_connect"))
    )
    (net (code "73") (name "unconnected-(DSUB1-Pad11)") (class "Default")
      (node (ref "DSUB1") (pin "11") (pinfunction "11_11") (pintype "input+no_connect"))
    )
    (net (code "74") (name "unconnected-(DSUB1-Pad12)") (class "Default")
      (node (ref "DSUB1") (pin "12") (pinfunction "12_12") (pintype "input+no_connect"))
    )
    (net (code "75") (name "unconnected-(DSUB1-Pad15)") (class "Default")
      (node (ref "DSUB1") (pin "15") (pinfunction "15_15") (pintype "input+no_connect"))
    )
    (net (code "76") (name "unconnected-(J2-Pad4)") (class "Default")
      (node (ref "J2") (pin "4") (pinfunction "4_4") (pintype "input+no_connect"))
    )
    (net (code "77") (name "unconnected-(PS1-PIN2-Pad2)") (class "Default")
      (node (ref "PS1") (pin "2") (pinfunction "PIN2_2") (pintype "input+no_connect"))
    )
    (net (code "78") (name "unconnected-(PS1-PIN6-Pad6)") (class "Default")
      (node (ref "PS1") (pin "6") (pinfunction "PIN6_6") (pintype "input+no_connect"))
    )
    (net (code "79") (name "unconnected-(U2-32kHz-Pad1)") (class "Default")
      (node (ref "U2") (pin "1") (pinfunction "32kHz_1") (pintype "input+no_connect"))
    )
    (net (code "80") (name "unconnected-(U2-INT#{slash}SQW-Pad3)") (class "Default")
      (node (ref "U2") (pin "3") (pinfunction "INT#/SQW_3") (pintype "bidirectional+no_connect"))
    )
    (net (code "81") (name "unconnected-(U5-SWCLK-Pad24)") (class "Default")
      (node (ref "U5") (pin "24") (pinfunction "SWCLK_24") (pintype "output+no_connect"))
    )
    (net (code "82") (name "unconnected-(U5-SWD-Pad25)") (class "Default")
      (node (ref "U5") (pin "25") (pinfunction "SWD_25") (pintype "bidirectional+no_connect"))
    )
    (net (code "83") (name "unconnected-(USB2-SUB1-PadA8)") (class "Default")
      (node (ref "USB2") (pin "A8") (pinfunction "SUB1_A8") (pintype "input+no_connect"))
    )
    (net (code "84") (name "unconnected-(USB2-SUB2-PadB8)") (class "Default")
      (node (ref "USB2") (pin "B8") (pinfunction "SUB2_B8") (pintype "input+no_connect"))
    )
  )
)
